# das_updated_v7.net
KiCad netlist of a schematic drawn in EAGLE
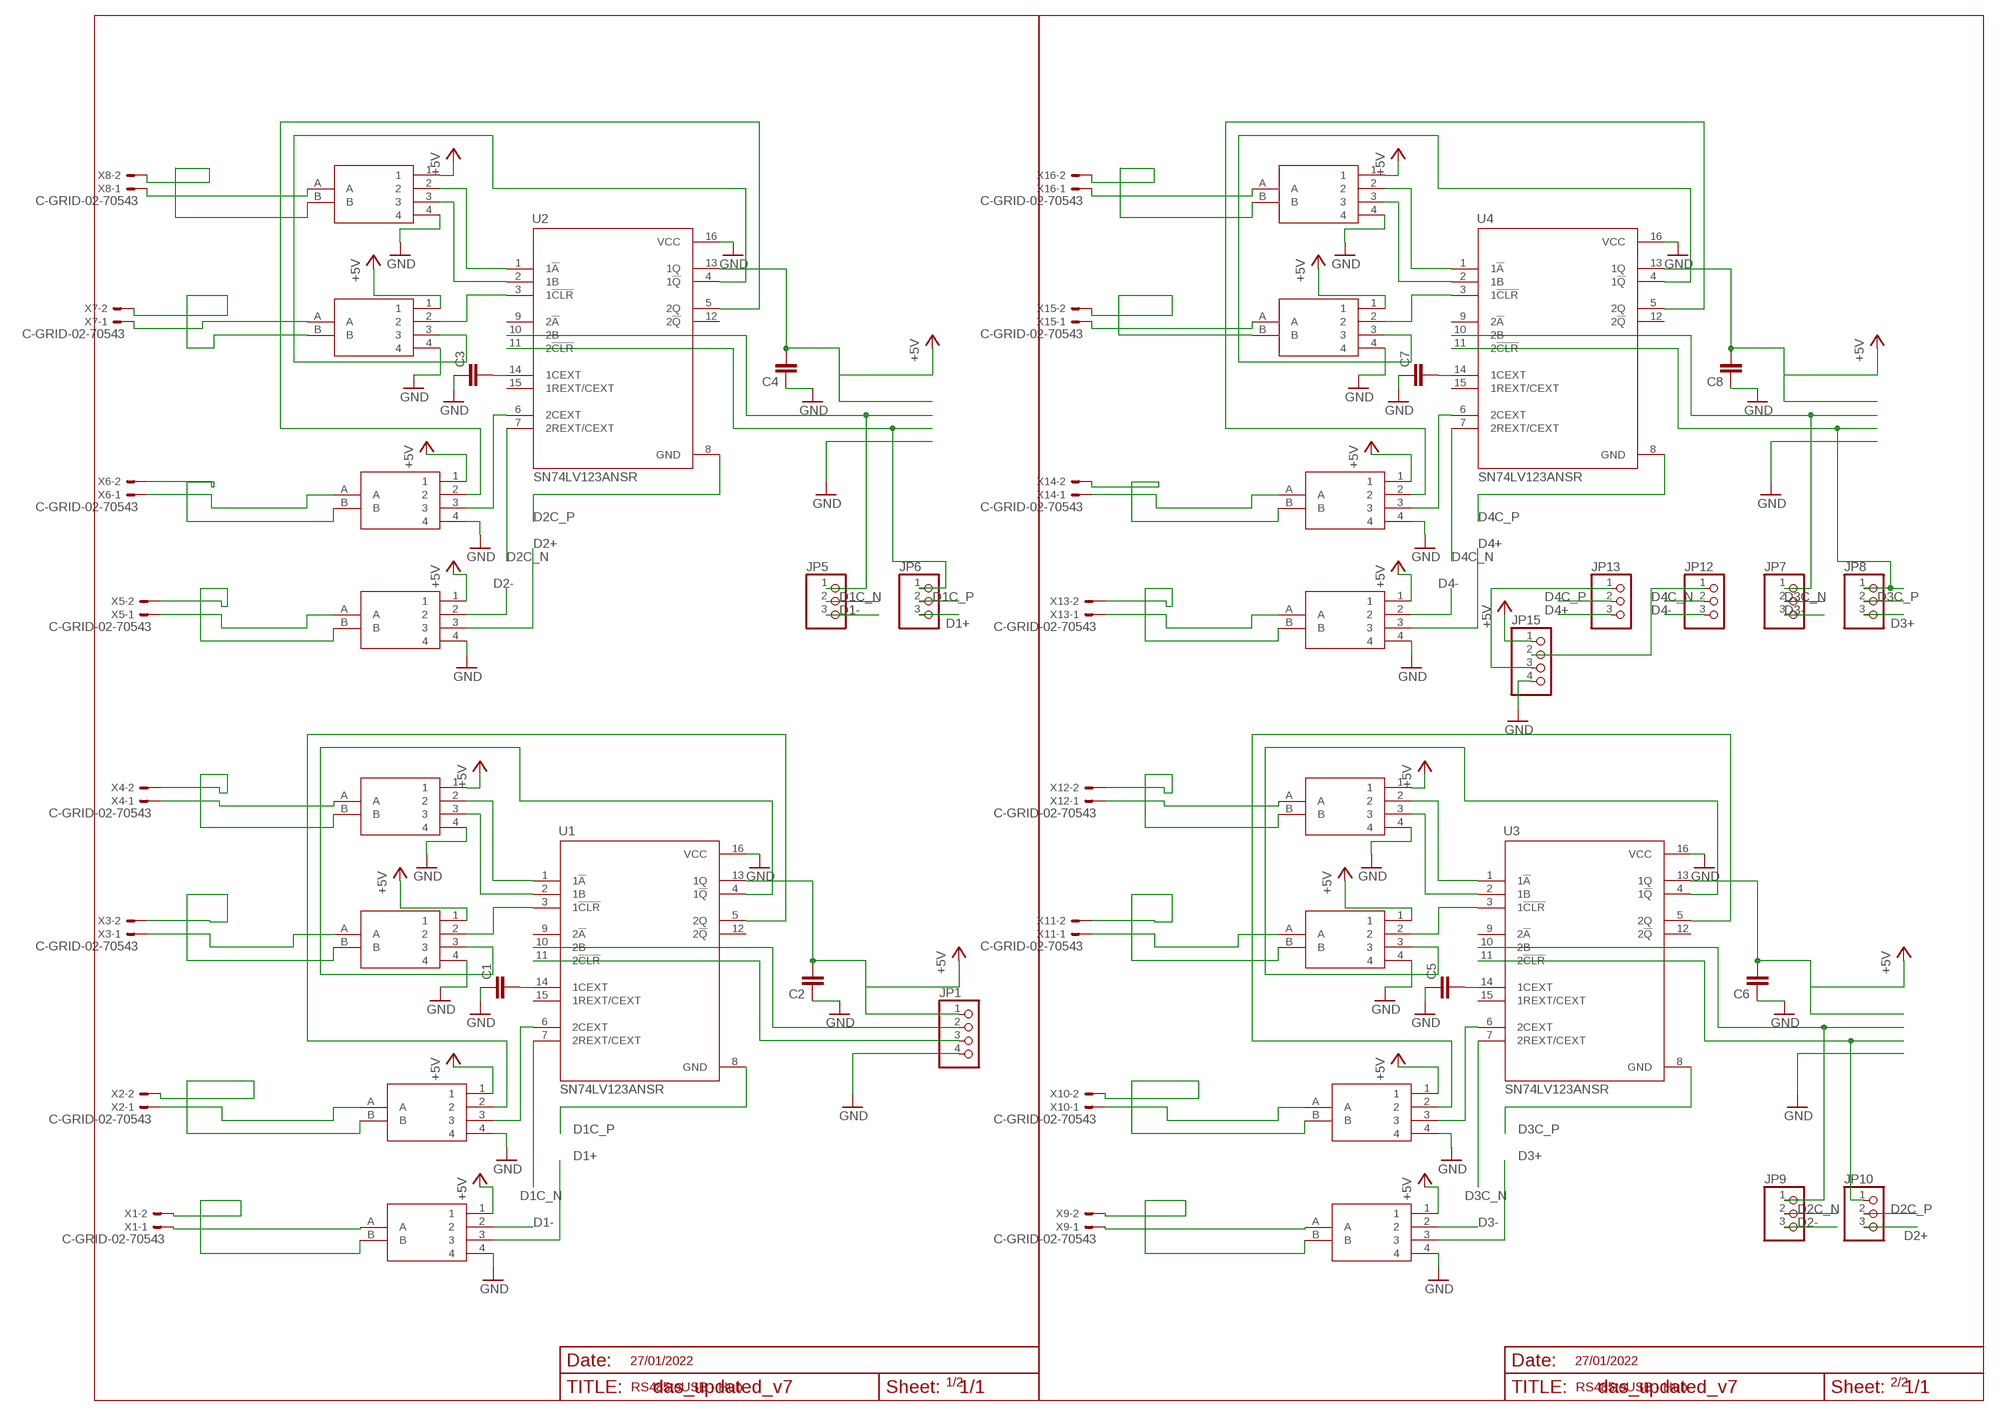
[diagram p0: schematic, sheet 1]

(export (version "E")
  (design (tool "Eeschema 10.0.6"))
  (components
    (comp (ref "C1")
      (value "C-EUC0603K")
      (footprint "eagle-import:C0603K")
      (libsource (lib "eagle-import") (part "C-EUC0603K"))
    )
    (comp (ref "C2")
      (value "C-EUC0603K")
      (footprint "eagle-import:C0603K")
      (libsource (lib "eagle-import") (part "C-EUC0603K"))
    )
    (comp (ref "C3")
      (value "C-EUC0603K")
      (footprint "eagle-import:C0603K")
      (libsource (lib "eagle-import") (part "C-EUC0603K"))
    )
    (comp (ref "C4")
      (value "C-EUC0603K")
      (footprint "eagle-import:C0603K")
      (libsource (lib "eagle-import") (part "C-EUC0603K"))
    )
    (comp (ref "C5")
      (value "C-EUC0603K")
      (footprint "eagle-import:C0603K")
      (libsource (lib "eagle-import") (part "C-EUC0603K"))
    )
    (comp (ref "C6")
      (value "C-EUC0603K")
      (footprint "eagle-import:C0603K")
      (libsource (lib "eagle-import") (part "C-EUC0603K"))
    )
    (comp (ref "C7")
      (value "C-EUC0603K")
      (footprint "eagle-import:C0603K")
      (libsource (lib "eagle-import") (part "C-EUC0603K"))
    )
    (comp (ref "C8")
      (value "C-EUC0603K")
      (footprint "eagle-import:C0603K")
      (libsource (lib "eagle-import") (part "C-EUC0603K"))
    )
    (comp (ref "JP1")
      (value "PINHD-1X4")
      (footprint "eagle-import:1X04")
      (libsource (lib "eagle-import") (part "PINHD-1X4"))
    )
    (comp (ref "JP5")
      (value "PINHD-1X3")
      (footprint "eagle-import:1X03")
      (libsource (lib "eagle-import") (part "PINHD-1X3"))
    )
    (comp (ref "JP6")
      (value "PINHD-1X3")
      (footprint "eagle-import:1X03")
      (libsource (lib "eagle-import") (part "PINHD-1X3"))
    )
    (comp (ref "JP7")
      (value "PINHD-1X3")
      (footprint "eagle-import:1X03")
      (libsource (lib "eagle-import") (part "PINHD-1X3"))
    )
    (comp (ref "JP8")
      (value "PINHD-1X3")
      (footprint "eagle-import:1X03")
      (libsource (lib "eagle-import") (part "PINHD-1X3"))
    )
    (comp (ref "JP9")
      (value "PINHD-1X3")
      (footprint "eagle-import:1X03")
      (libsource (lib "eagle-import") (part "PINHD-1X3"))
    )
    (comp (ref "JP10")
      (value "PINHD-1X3")
      (footprint "eagle-import:1X03")
      (libsource (lib "eagle-import") (part "PINHD-1X3"))
    )
    (comp (ref "JP12")
      (value "PINHD-1X3")
      (footprint "eagle-import:1X03")
      (libsource (lib "eagle-import") (part "PINHD-1X3"))
    )
    (comp (ref "JP13")
      (value "PINHD-1X3")
      (footprint "eagle-import:1X03")
      (libsource (lib "eagle-import") (part "PINHD-1X3"))
    )
    (comp (ref "JP15")
      (value "PINHD-1X4")
      (footprint "eagle-import:1X04")
      (libsource (lib "eagle-import") (part "PINHD-1X4"))
    )
    (comp (ref "U1")
      (value "SN74LV123ANSR")
      (footprint "eagle-import:SOIC127P780X200-16N")
      (fields (field (name "MF") "Texas Instruments"))
      (libsource (lib "eagle-import") (part "SN74LV123ANSR"))
    )
    (comp (ref "U2")
      (value "SN74LV123ANSR")
      (footprint "eagle-import:SOIC127P780X200-16N")
      (fields (field (name "MF") "Texas Instruments"))
      (libsource (lib "eagle-import") (part "SN74LV123ANSR"))
    )
    (comp (ref "U3")
      (value "SN74LV123ANSR")
      (footprint "eagle-import:SOIC127P780X200-16N")
      (fields (field (name "MF") "Texas Instruments"))
      (libsource (lib "eagle-import") (part "SN74LV123ANSR"))
    )
    (comp (ref "U4")
      (value "SN74LV123ANSR")
      (footprint "eagle-import:SOIC127P780X200-16N")
      (fields (field (name "MF") "Texas Instruments"))
      (libsource (lib "eagle-import") (part "SN74LV123ANSR"))
    )
    (comp (ref "USB2RS1")
      (value "USB2RS485")
      (footprint "eagle-import:USB2RS485")
      (libsource (lib "eagle-import") (part "USB2RS485"))
    )
    (comp (ref "USB2RS2")
      (value "USB2RS485")
      (footprint "eagle-import:USB2RS485")
      (libsource (lib "eagle-import") (part "USB2RS485"))
    )
    (comp (ref "USB2RS3")
      (value "USB2RS485")
      (footprint "eagle-import:USB2RS485")
      (libsource (lib "eagle-import") (part "USB2RS485"))
    )
    (comp (ref "USB2RS4")
      (value "USB2RS485")
      (footprint "eagle-import:USB2RS485")
      (libsource (lib "eagle-import") (part "USB2RS485"))
    )
    (comp (ref "USB2RS5")
      (value "USB2RS485")
      (footprint "eagle-import:USB2RS485")
      (libsource (lib "eagle-import") (part "USB2RS485"))
    )
    (comp (ref "USB2RS6")
      (value "USB2RS485")
      (footprint "eagle-import:USB2RS485")
      (libsource (lib "eagle-import") (part "USB2RS485"))
    )
    (comp (ref "USB2RS7")
      (value "USB2RS485")
      (footprint "eagle-import:USB2RS485")
      (libsource (lib "eagle-import") (part "USB2RS485"))
    )
    (comp (ref "USB2RS8")
      (value "USB2RS485")
      (footprint "eagle-import:USB2RS485")
      (libsource (lib "eagle-import") (part "USB2RS485"))
    )
    (comp (ref "USB2RS9")
      (value "USB2RS485")
      (footprint "eagle-import:USB2RS485")
      (libsource (lib "eagle-import") (part "USB2RS485"))
    )
    (comp (ref "USB2RS10")
      (value "USB2RS485")
      (footprint "eagle-import:USB2RS485")
      (libsource (lib "eagle-import") (part "USB2RS485"))
    )
    (comp (ref "USB2RS11")
      (value "USB2RS485")
      (footprint "eagle-import:USB2RS485")
      (libsource (lib "eagle-import") (part "USB2RS485"))
    )
    (comp (ref "USB2RS12")
      (value "USB2RS485")
      (footprint "eagle-import:USB2RS485")
      (libsource (lib "eagle-import") (part "USB2RS485"))
    )
    (comp (ref "USB2RS13")
      (value "USB2RS485")
      (footprint "eagle-import:USB2RS485")
      (libsource (lib "eagle-import") (part "USB2RS485"))
    )
    (comp (ref "USB2RS14")
      (value "USB2RS485")
      (footprint "eagle-import:USB2RS485")
      (libsource (lib "eagle-import") (part "USB2RS485"))
    )
    (comp (ref "USB2RS15")
      (value "USB2RS485")
      (footprint "eagle-import:USB2RS485")
      (libsource (lib "eagle-import") (part "USB2RS485"))
    )
    (comp (ref "USB2RS16")
      (value "USB2RS485")
      (footprint "eagle-import:USB2RS485")
      (libsource (lib "eagle-import") (part "USB2RS485"))
    )
    (comp (ref "X1")
      (value "C-GRID-02-70543")
      (footprint "eagle-import:70543-02")
      (fields (field (name "MF") "MOLEX"))
      (libsource (lib "eagle-import") (part "C-GRID-02-70543"))
    )
    (comp (ref "X2")
      (value "C-GRID-02-70543")
      (footprint "eagle-import:70543-02")
      (fields (field (name "MF") "MOLEX"))
      (libsource (lib "eagle-import") (part "C-GRID-02-70543"))
    )
    (comp (ref "X3")
      (value "C-GRID-02-70543")
      (footprint "eagle-import:70543-02")
      (fields (field (name "MF") "MOLEX"))
      (libsource (lib "eagle-import") (part "C-GRID-02-70543"))
    )
    (comp (ref "X4")
      (value "C-GRID-02-70543")
      (footprint "eagle-import:70543-02")
      (fields (field (name "MF") "MOLEX"))
      (libsource (lib "eagle-import") (part "C-GRID-02-70543"))
    )
    (comp (ref "X5")
      (value "C-GRID-02-70543")
      (footprint "eagle-import:70543-02")
      (fields (field (name "MF") "MOLEX"))
      (libsource (lib "eagle-import") (part "C-GRID-02-70543"))
    )
    (comp (ref "X6")
      (value "C-GRID-02-70543")
      (footprint "eagle-import:70543-02")
      (fields (field (name "MF") "MOLEX"))
      (libsource (lib "eagle-import") (part "C-GRID-02-70543"))
    )
    (comp (ref "X7")
      (value "C-GRID-02-70543")
      (footprint "eagle-import:70543-02")
      (fields (field (name "MF") "MOLEX"))
      (libsource (lib "eagle-import") (part "C-GRID-02-70543"))
    )
    (comp (ref "X8")
      (value "C-GRID-02-70543")
      (footprint "eagle-import:70543-02")
      (fields (field (name "MF") "MOLEX"))
      (libsource (lib "eagle-import") (part "C-GRID-02-70543"))
    )
    (comp (ref "X9")
      (value "C-GRID-02-70543")
      (footprint "eagle-import:70543-02")
      (fields (field (name "MF") "MOLEX"))
      (libsource (lib "eagle-import") (part "C-GRID-02-70543"))
    )
    (comp (ref "X10")
      (value "C-GRID-02-70543")
      (footprint "eagle-import:70543-02")
      (fields (field (name "MF") "MOLEX"))
      (libsource (lib "eagle-import") (part "C-GRID-02-70543"))
    )
    (comp (ref "X11")
      (value "C-GRID-02-70543")
      (footprint "eagle-import:70543-02")
      (fields (field (name "MF") "MOLEX"))
      (libsource (lib "eagle-import") (part "C-GRID-02-70543"))
    )
    (comp (ref "X12")
      (value "C-GRID-02-70543")
      (footprint "eagle-import:70543-02")
      (fields (field (name "MF") "MOLEX"))
      (libsource (lib "eagle-import") (part "C-GRID-02-70543"))
    )
    (comp (ref "X13")
      (value "C-GRID-02-70543")
      (footprint "eagle-import:70543-02")
      (fields (field (name "MF") "MOLEX"))
      (libsource (lib "eagle-import") (part "C-GRID-02-70543"))
    )
    (comp (ref "X14")
      (value "C-GRID-02-70543")
      (footprint "eagle-import:70543-02")
      (fields (field (name "MF") "MOLEX"))
      (libsource (lib "eagle-import") (part "C-GRID-02-70543"))
    )
    (comp (ref "X15")
      (value "C-GRID-02-70543")
      (footprint "eagle-import:70543-02")
      (fields (field (name "MF") "MOLEX"))
      (libsource (lib "eagle-import") (part "C-GRID-02-70543"))
    )
    (comp (ref "X16")
      (value "C-GRID-02-70543")
      (footprint "eagle-import:70543-02")
      (fields (field (name "MF") "MOLEX"))
      (libsource (lib "eagle-import") (part "C-GRID-02-70543"))
    )
  )
  (nets
    (net (code "1") (name "+5V") (class "Default")
      (node (ref "C2") (pin "2") (pinfunction "2_2") (pintype "passive"))
      (node (ref "C4") (pin "2") (pinfunction "2_2") (pintype "passive"))
      (node (ref "C6") (pin "2") (pinfunction "2_2") (pintype "passive"))
      (node (ref "C8") (pin "2") (pinfunction "2_2") (pintype "passive"))
      (node (ref "JP1") (pin "1") (pinfunction "1_1") (pintype "passive"))
      (node (ref "JP15") (pin "1") (pinfunction "1_1") (pintype "passive"))
      (node (ref "U1") (pin "13") (pinfunction "1Q_13") (pintype "output"))
      (node (ref "U2") (pin "13") (pinfunction "1Q_13") (pintype "output"))
      (node (ref "U3") (pin "13") (pinfunction "1Q_13") (pintype "output"))
      (node (ref "U4") (pin "13") (pinfunction "1Q_13") (pintype "output"))
      (node (ref "USB2RS1") (pin "1") (pinfunction "1_1") (pintype "bidirectional"))
      (node (ref "USB2RS10") (pin "1") (pinfunction "1_1") (pintype "bidirectional"))
      (node (ref "USB2RS11") (pin "1") (pinfunction "1_1") (pintype "bidirectional"))
      (node (ref "USB2RS12") (pin "1") (pinfunction "1_1") (pintype "bidirectional"))
      (node (ref "USB2RS13") (pin "1") (pinfunction "1_1") (pintype "bidirectional"))
      (node (ref "USB2RS14") (pin "1") (pinfunction "1_1") (pintype "bidirectional"))
      (node (ref "USB2RS15") (pin "1") (pinfunction "1_1") (pintype "bidirectional"))
      (node (ref "USB2RS16") (pin "1") (pinfunction "1_1") (pintype "bidirectional"))
      (node (ref "USB2RS2") (pin "1") (pinfunction "1_1") (pintype "bidirectional"))
      (node (ref "USB2RS3") (pin "1") (pinfunction "1_1") (pintype "bidirectional"))
      (node (ref "USB2RS4") (pin "1") (pinfunction "1_1") (pintype "bidirectional"))
      (node (ref "USB2RS5") (pin "1") (pinfunction "1_1") (pintype "bidirectional"))
      (node (ref "USB2RS6") (pin "1") (pinfunction "1_1") (pintype "bidirectional"))
      (node (ref "USB2RS7") (pin "1") (pinfunction "1_1") (pintype "bidirectional"))
      (node (ref "USB2RS8") (pin "1") (pinfunction "1_1") (pintype "bidirectional"))
      (node (ref "USB2RS9") (pin "1") (pinfunction "1_1") (pintype "bidirectional"))
    )
    (net (code "2") (name "/D1+") (class "Default")
      (node (ref "JP6") (pin "3") (pinfunction "3_3") (pintype "passive"))
      (node (ref "USB2RS4") (pin "3") (pinfunction "3_3") (pintype "bidirectional"))
    )
    (net (code "3") (name "/D1-") (class "Default")
      (node (ref "JP5") (pin "3") (pinfunction "3_3") (pintype "passive"))
      (node (ref "USB2RS4") (pin "2") (pinfunction "2_2") (pintype "bidirectional"))
    )
    (net (code "4") (name "/D1C_N") (class "Default")
      (node (ref "JP5") (pin "2") (pinfunction "2_2") (pintype "passive"))
      (node (ref "U1") (pin "7") (pinfunction "2REXT/CEXT_7") (pintype "bidirectional"))
    )
    (net (code "5") (name "/D1C_P") (class "Default")
      (node (ref "JP6") (pin "2") (pinfunction "2_2") (pintype "passive"))
      (node (ref "U1") (pin "8") (pinfunction "GND_8") (pintype "power_in"))
    )
    (net (code "6") (name "/D2+") (class "Default")
      (node (ref "JP10") (pin "3") (pinfunction "3_3") (pintype "passive"))
      (node (ref "USB2RS8") (pin "3") (pinfunction "3_3") (pintype "bidirectional"))
    )
    (net (code "7") (name "/D2-") (class "Default")
      (node (ref "JP9") (pin "3") (pinfunction "3_3") (pintype "passive"))
      (node (ref "USB2RS8") (pin "2") (pinfunction "2_2") (pintype "bidirectional"))
    )
    (net (code "8") (name "/D2C_N") (class "Default")
      (node (ref "JP9") (pin "2") (pinfunction "2_2") (pintype "passive"))
      (node (ref "U2") (pin "7") (pinfunction "2REXT/CEXT_7") (pintype "bidirectional"))
    )
    (net (code "9") (name "/D2C_P") (class "Default")
      (node (ref "JP10") (pin "2") (pinfunction "2_2") (pintype "passive"))
      (node (ref "U2") (pin "8") (pinfunction "GND_8") (pintype "power_in"))
    )
    (net (code "10") (name "/D3+") (class "Default")
      (node (ref "JP8") (pin "3") (pinfunction "3_3") (pintype "passive"))
      (node (ref "USB2RS12") (pin "3") (pinfunction "3_3") (pintype "bidirectional"))
    )
    (net (code "11") (name "/D3-") (class "Default")
      (node (ref "JP7") (pin "3") (pinfunction "3_3") (pintype "passive"))
      (node (ref "USB2RS12") (pin "2") (pinfunction "2_2") (pintype "bidirectional"))
    )
    (net (code "12") (name "/D3C_N") (class "Default")
      (node (ref "JP7") (pin "2") (pinfunction "2_2") (pintype "passive"))
      (node (ref "U3") (pin "7") (pinfunction "2REXT/CEXT_7") (pintype "bidirectional"))
    )
    (net (code "13") (name "/D3C_P") (class "Default")
      (node (ref "JP8") (pin "2") (pinfunction "2_2") (pintype "passive"))
      (node (ref "U3") (pin "8") (pinfunction "GND_8") (pintype "power_in"))
    )
    (net (code "14") (name "/D4+") (class "Default")
      (node (ref "JP13") (pin "3") (pinfunction "3_3") (pintype "passive"))
      (node (ref "USB2RS16") (pin "3") (pinfunction "3_3") (pintype "bidirectional"))
    )
    (net (code "15") (name "/D4-") (class "Default")
      (node (ref "JP12") (pin "3") (pinfunction "3_3") (pintype "passive"))
      (node (ref "USB2RS16") (pin "2") (pinfunction "2_2") (pintype "bidirectional"))
    )
    (net (code "16") (name "/D4C_N") (class "Default")
      (node (ref "JP12") (pin "2") (pinfunction "2_2") (pintype "passive"))
      (node (ref "U4") (pin "7") (pinfunction "2REXT/CEXT_7") (pintype "bidirectional"))
    )
    (net (code "17") (name "/D4C_P") (class "Default")
      (node (ref "JP13") (pin "2") (pinfunction "2_2") (pintype "passive"))
      (node (ref "U4") (pin "8") (pinfunction "GND_8") (pintype "power_in"))
    )
    (net (code "18") (name "GND") (class "Default")
      (node (ref "C1") (pin "1") (pinfunction "1_1") (pintype "passive"))
      (node (ref "C2") (pin "1") (pinfunction "1_1") (pintype "passive"))
      (node (ref "C3") (pin "1") (pinfunction "1_1") (pintype "passive"))
      (node (ref "C4") (pin "1") (pinfunction "1_1") (pintype "passive"))
      (node (ref "C5") (pin "1") (pinfunction "1_1") (pintype "passive"))
      (node (ref "C6") (pin "1") (pinfunction "1_1") (pintype "passive"))
      (node (ref "C7") (pin "1") (pinfunction "1_1") (pintype "passive"))
      (node (ref "C8") (pin "1") (pinfunction "1_1") (pintype "passive"))
      (node (ref "JP1") (pin "4") (pinfunction "4_4") (pintype "passive"))
      (node (ref "JP15") (pin "4") (pinfunction "4_4") (pintype "passive"))
      (node (ref "U1") (pin "16") (pinfunction "VCC_16") (pintype "power_in"))
      (node (ref "U2") (pin "16") (pinfunction "VCC_16") (pintype "power_in"))
      (node (ref "U3") (pin "16") (pinfunction "VCC_16") (pintype "power_in"))
      (node (ref "U4") (pin "16") (pinfunction "VCC_16") (pintype "power_in"))
      (node (ref "USB2RS1") (pin "4") (pinfunction "4_4") (pintype "bidirectional"))
      (node (ref "USB2RS10") (pin "4") (pinfunction "4_4") (pintype "bidirectional"))
      (node (ref "USB2RS11") (pin "4") (pinfunction "4_4") (pintype "bidirectional"))
      (node (ref "USB2RS12") (pin "4") (pinfunction "4_4") (pintype "bidirectional"))
      (node (ref "USB2RS13") (pin "4") (pinfunction "4_4") (pintype "bidirectional"))
      (node (ref "USB2RS14") (pin "4") (pinfunction "4_4") (pintype "bidirectional"))
      (node (ref "USB2RS15") (pin "4") (pinfunction "4_4") (pintype "bidirectional"))
      (node (ref "USB2RS16") (pin "4") (pinfunction "4_4") (pintype "bidirectional"))
      (node (ref "USB2RS2") (pin "4") (pinfunction "4_4") (pintype "bidirectional"))
      (node (ref "USB2RS3") (pin "4") (pinfunction "4_4") (pintype "bidirectional"))
      (node (ref "USB2RS4") (pin "4") (pinfunction "4_4") (pintype "bidirectional"))
      (node (ref "USB2RS5") (pin "4") (pinfunction "4_4") (pintype "bidirectional"))
      (node (ref "USB2RS6") (pin "4") (pinfunction "4_4") (pintype "bidirectional"))
      (node (ref "USB2RS7") (pin "4") (pinfunction "4_4") (pintype "bidirectional"))
      (node (ref "USB2RS8") (pin "4") (pinfunction "4_4") (pintype "bidirectional"))
      (node (ref "USB2RS9") (pin "4") (pinfunction "4_4") (pintype "bidirectional"))
    )
    (net (code "19") (name "Net-(JP12-Pad1)") (class "Default")
      (node (ref "JP12") (pin "1") (pinfunction "1_1") (pintype "passive"))
      (node (ref "JP15") (pin "2") (pinfunction "2_2") (pintype "passive"))
    )
    (net (code "20") (name "Net-(JP13-Pad1)") (class "Default")
      (node (ref "JP13") (pin "1") (pinfunction "1_1") (pintype "passive"))
      (node (ref "JP15") (pin "3") (pinfunction "3_3") (pintype "passive"))
    )
    (net (code "21") (name "Net-(U1-1B)") (class "Default")
      (node (ref "U1") (pin "2") (pinfunction "1B_2") (pintype "input"))
      (node (ref "USB2RS1") (pin "3") (pinfunction "3_3") (pintype "bidirectional"))
    )
    (net (code "22") (name "Net-(U1-1CEXT)") (class "Default")
      (node (ref "C1") (pin "2") (pinfunction "2_2") (pintype "passive"))
      (node (ref "U1") (pin "14") (pinfunction "1CEXT_14") (pintype "bidirectional"))
    )
    (net (code "23") (name "Net-(U1-1~{A})") (class "Default")
      (node (ref "U1") (pin "1") (pinfunction "1~{A}_1") (pintype "input"))
      (node (ref "USB2RS1") (pin "2") (pinfunction "2_2") (pintype "bidirectional"))
    )
    (net (code "24") (name "Net-(U1-1~{CLR})") (class "Default")
      (node (ref "U1") (pin "3") (pinfunction "1~{CLR}_3") (pintype "input"))
      (node (ref "USB2RS2") (pin "2") (pinfunction "2_2") (pintype "bidirectional"))
    )
    (net (code "25") (name "Net-(U1-1~{Q})") (class "Default")
      (node (ref "U1") (pin "4") (pinfunction "1~{Q}_4") (pintype "output"))
      (node (ref "USB2RS2") (pin "3") (pinfunction "3_3") (pintype "bidirectional"))
    )
    (net (code "26") (name "Net-(U1-2B)") (class "Default")
      (node (ref "JP1") (pin "2") (pinfunction "2_2") (pintype "passive"))
      (node (ref "U1") (pin "10") (pinfunction "2B_10") (pintype "input"))
    )
    (net (code "27") (name "Net-(U1-2CEXT)") (class "Default")
      (node (ref "U1") (pin "6") (pinfunction "2CEXT_6") (pintype "bidirectional"))
      (node (ref "USB2RS3") (pin "3") (pinfunction "3_3") (pintype "bidirectional"))
    )
    (net (code "28") (name "Net-(U1-2Q)") (class "Default")
      (node (ref "U1") (pin "5") (pinfunction "2Q_5") (pintype "output"))
      (node (ref "USB2RS3") (pin "2") (pinfunction "2_2") (pintype "bidirectional"))
    )
    (net (code "29") (name "Net-(U1-2~{CLR})") (class "Default")
      (node (ref "JP1") (pin "3") (pinfunction "3_3") (pintype "passive"))
      (node (ref "U1") (pin "11") (pinfunction "2~{CLR}_11") (pintype "input"))
    )
    (net (code "30") (name "Net-(U2-1B)") (class "Default")
      (node (ref "U2") (pin "2") (pinfunction "1B_2") (pintype "input"))
      (node (ref "USB2RS5") (pin "3") (pinfunction "3_3") (pintype "bidirectional"))
    )
    (net (code "31") (name "Net-(U2-1CEXT)") (class "Default")
      (node (ref "C3") (pin "2") (pinfunction "2_2") (pintype "passive"))
      (node (ref "U2") (pin "14") (pinfunction "1CEXT_14") (pintype "bidirectional"))
    )
    (net (code "32") (name "Net-(U2-1~{A})") (class "Default")
      (node (ref "U2") (pin "1") (pinfunction "1~{A}_1") (pintype "input"))
      (node (ref "USB2RS5") (pin "2") (pinfunction "2_2") (pintype "bidirectional"))
    )
    (net (code "33") (name "Net-(U2-1~{CLR})") (class "Default")
      (node (ref "U2") (pin "3") (pinfunction "1~{CLR}_3") (pintype "input"))
      (node (ref "USB2RS6") (pin "2") (pinfunction "2_2") (pintype "bidirectional"))
    )
    (net (code "34") (name "Net-(U2-1~{Q})") (class "Default")
      (node (ref "U2") (pin "4") (pinfunction "1~{Q}_4") (pintype "output"))
      (node (ref "USB2RS6") (pin "3") (pinfunction "3_3") (pintype "bidirectional"))
    )
    (net (code "35") (name "Net-(U2-2B)") (class "Default")
      (node (ref "JP5") (pin "1") (pinfunction "1_1") (pintype "passive"))
      (node (ref "U2") (pin "10") (pinfunction "2B_10") (pintype "input"))
    )
    (net (code "36") (name "Net-(U2-2CEXT)") (class "Default")
      (node (ref "U2") (pin "6") (pinfunction "2CEXT_6") (pintype "bidirectional"))
      (node (ref "USB2RS7") (pin "3") (pinfunction "3_3") (pintype "bidirectional"))
    )
    (net (code "37") (name "Net-(U2-2Q)") (class "Default")
      (node (ref "U2") (pin "5") (pinfunction "2Q_5") (pintype "output"))
      (node (ref "USB2RS7") (pin "2") (pinfunction "2_2") (pintype "bidirectional"))
    )
    (net (code "38") (name "Net-(U2-2~{CLR})") (class "Default")
      (node (ref "JP6") (pin "1") (pinfunction "1_1") (pintype "passive"))
      (node (ref "U2") (pin "11") (pinfunction "2~{CLR}_11") (pintype "input"))
    )
    (net (code "39") (name "Net-(U3-1B)") (class "Default")
      (node (ref "U3") (pin "2") (pinfunction "1B_2") (pintype "input"))
      (node (ref "USB2RS9") (pin "3") (pinfunction "3_3") (pintype "bidirectional"))
    )
    (net (code "40") (name "Net-(U3-1CEXT)") (class "Default")
      (node (ref "C5") (pin "2") (pinfunction "2_2") (pintype "passive"))
      (node (ref "U3") (pin "14") (pinfunction "1CEXT_14") (pintype "bidirectional"))
    )
    (net (code "41") (name "Net-(U3-1~{A})") (class "Default")
      (node (ref "U3") (pin "1") (pinfunction "1~{A}_1") (pintype "input"))
      (node (ref "USB2RS9") (pin "2") (pinfunction "2_2") (pintype "bidirectional"))
    )
    (net (code "42") (name "Net-(U3-1~{CLR})") (class "Default")
      (node (ref "U3") (pin "3") (pinfunction "1~{CLR}_3") (pintype "input"))
      (node (ref "USB2RS10") (pin "2") (pinfunction "2_2") (pintype "bidirectional"))
    )
    (net (code "43") (name "Net-(U3-1~{Q})") (class "Default")
      (node (ref "U3") (pin "4") (pinfunction "1~{Q}_4") (pintype "output"))
      (node (ref "USB2RS10") (pin "3") (pinfunction "3_3") (pintype "bidirectional"))
    )
    (net (code "44") (name "Net-(U3-2B)") (class "Default")
      (node (ref "JP9") (pin "1") (pinfunction "1_1") (pintype "passive"))
      (node (ref "U3") (pin "10") (pinfunction "2B_10") (pintype "input"))
    )
    (net (code "45") (name "Net-(U3-2CEXT)") (class "Default")
      (node (ref "U3") (pin "6") (pinfunction "2CEXT_6") (pintype "bidirectional"))
      (node (ref "USB2RS11") (pin "3") (pinfunction "3_3") (pintype "bidirectional"))
    )
    (net (code "46") (name "Net-(U3-2Q)") (class "Default")
      (node (ref "U3") (pin "5") (pinfunction "2Q_5") (pintype "output"))
      (node (ref "USB2RS11") (pin "2") (pinfunction "2_2") (pintype "bidirectional"))
    )
    (net (code "47") (name "Net-(U3-2~{CLR})") (class "Default")
      (node (ref "JP10") (pin "1") (pinfunction "1_1") (pintype "passive"))
      (node (ref "U3") (pin "11") (pinfunction "2~{CLR}_11") (pintype "input"))
    )
    (net (code "48") (name "Net-(U4-1B)") (class "Default")
      (node (ref "U4") (pin "2") (pinfunction "1B_2") (pintype "input"))
      (node (ref "USB2RS13") (pin "3") (pinfunction "3_3") (pintype "bidirectional"))
    )
    (net (code "49") (name "Net-(U4-1CEXT)") (class "Default")
      (node (ref "C7") (pin "2") (pinfunction "2_2") (pintype "passive"))
      (node (ref "U4") (pin "14") (pinfunction "1CEXT_14") (pintype "bidirectional"))
    )
    (net (code "50") (name "Net-(U4-1~{A})") (class "Default")
      (node (ref "U4") (pin "1") (pinfunction "1~{A}_1") (pintype "input"))
      (node (ref "USB2RS13") (pin "2") (pinfunction "2_2") (pintype "bidirectional"))
    )
    (net (code "51") (name "Net-(U4-1~{CLR})") (class "Default")
      (node (ref "U4") (pin "3") (pinfunction "1~{CLR}_3") (pintype "input"))
      (node (ref "USB2RS14") (pin "2") (pinfunction "2_2") (pintype "bidirectional"))
    )
    (net (code "52") (name "Net-(U4-1~{Q})") (class "Default")
      (node (ref "U4") (pin "4") (pinfunction "1~{Q}_4") (pintype "output"))
      (node (ref "USB2RS14") (pin "3") (pinfunction "3_3") (pintype "bidirectional"))
    )
    (net (code "53") (name "Net-(U4-2B)") (class "Default")
      (node (ref "JP7") (pin "1") (pinfunction "1_1") (pintype "passive"))
      (node (ref "U4") (pin "10") (pinfunction "2B_10") (pintype "input"))
    )
    (net (code "54") (name "Net-(U4-2CEXT)") (class "Default")
      (node (ref "U4") (pin "6") (pinfunction "2CEXT_6") (pintype "bidirectional"))
      (node (ref "USB2RS15") (pin "3") (pinfunction "3_3") (pintype "bidirectional"))
    )
    (net (code "55") (name "Net-(U4-2Q)") (class "Default")
      (node (ref "U4") (pin "5") (pinfunction "2Q_5") (pintype "output"))
      (node (ref "USB2RS15") (pin "2") (pinfunction "2_2") (pintype "bidirectional"))
    )
    (net (code "56") (name "Net-(U4-2~{CLR})") (class "Default")
      (node (ref "JP8") (pin "1") (pinfunction "1_1") (pintype "passive"))
      (node (ref "U4") (pin "11") (pinfunction "2~{CLR}_11") (pintype "input"))
    )
    (net (code "57") (name "Net-(X1A-S)") (class "Default")
      (node (ref "USB2RS4") (pin "A") (pinfunction "A_A") (pintype "bidirectional"))
      (node (ref "X1") (pin "1") (pinfunction "S_1") (pintype "passive"))
    )
    (net (code "58") (name "Net-(X1B-S)") (class "Default")
      (node (ref "USB2RS4") (pin "B") (pinfunction "B_B") (pintype "bidirectional"))
      (node (ref "X1") (pin "2") (pinfunction "S_2") (pintype "passive"))
    )
    (net (code "59") (name "Net-(X2A-S)") (class "Default")
      (node (ref "USB2RS3") (pin "A") (pinfunction "A_A") (pintype "bidirectional"))
      (node (ref "X2") (pin "1") (pinfunction "S_1") (pintype "passive"))
    )
    (net (code "60") (name "Net-(X2B-S)") (class "Default")
      (node (ref "USB2RS3") (pin "B") (pinfunction "B_B") (pintype "bidirectional"))
      (node (ref "X2") (pin "2") (pinfunction "S_2") (pintype "passive"))
    )
    (net (code "61") (name "Net-(X3A-S)") (class "Default")
      (node (ref "USB2RS2") (pin "A") (pinfunction "A_A") (pintype "bidirectional"))
      (node (ref "X3") (pin "1") (pinfunction "S_1") (pintype "passive"))
    )
    (net (code "62") (name "Net-(X3B-S)") (class "Default")
      (node (ref "USB2RS2") (pin "B") (pinfunction "B_B") (pintype "bidirectional"))
      (node (ref "X3") (pin "2") (pinfunction "S_2") (pintype "passive"))
    )
    (net (code "63") (name "Net-(X4A-S)") (class "Default")
      (node (ref "USB2RS1") (pin "A") (pinfunction "A_A") (pintype "bidirectional"))
      (node (ref "X4") (pin "1") (pinfunction "S_1") (pintype "passive"))
    )
    (net (code "64") (name "Net-(X4B-S)") (class "Default")
      (node (ref "USB2RS1") (pin "B") (pinfunction "B_B") (pintype "bidirectional"))
      (node (ref "X4") (pin "2") (pinfunction "S_2") (pintype "passive"))
    )
    (net (code "65") (name "Net-(X5A-S)") (class "Default")
      (node (ref "USB2RS8") (pin "A") (pinfunction "A_A") (pintype "bidirectional"))
      (node (ref "X5") (pin "1") (pinfunction "S_1") (pintype "passive"))
    )
    (net (code "66") (name "Net-(X5B-S)") (class "Default")
      (node (ref "USB2RS8") (pin "B") (pinfunction "B_B") (pintype "bidirectional"))
      (node (ref "X5") (pin "2") (pinfunction "S_2") (pintype "passive"))
    )
    (net (code "67") (name "Net-(X6A-S)") (class "Default")
      (node (ref "USB2RS7") (pin "A") (pinfunction "A_A") (pintype "bidirectional"))
      (node (ref "X6") (pin "1") (pinfunction "S_1") (pintype "passive"))
    )
    (net (code "68") (name "Net-(X6B-S)") (class "Default")
      (node (ref "USB2RS7") (pin "B") (pinfunction "B_B") (pintype "bidirectional"))
      (node (ref "X6") (pin "2") (pinfunction "S_2") (pintype "passive"))
    )
    (net (code "69") (name "Net-(X7A-S)") (class "Default")
      (node (ref "USB2RS6") (pin "A") (pinfunction "A_A") (pintype "bidirectional"))
      (node (ref "X7") (pin "1") (pinfunction "S_1") (pintype "passive"))
    )
    (net (code "70") (name "Net-(X7B-S)") (class "Default")
      (node (ref "USB2RS6") (pin "B") (pinfunction "B_B") (pintype "bidirectional"))
      (node (ref "X7") (pin "2") (pinfunction "S_2") (pintype "passive"))
    )
    (net (code "71") (name "Net-(X8A-S)") (class "Default")
      (node (ref "USB2RS5") (pin "A") (pinfunction "A_A") (pintype "bidirectional"))
      (node (ref "X8") (pin "1") (pinfunction "S_1") (pintype "passive"))
    )
    (net (code "72") (name "Net-(X8B-S)") (class "Default")
      (node (ref "USB2RS5") (pin "B") (pinfunction "B_B") (pintype "bidirectional"))
      (node (ref "X8") (pin "2") (pinfunction "S_2") (pintype "passive"))
    )
    (net (code "73") (name "Net-(X9A-S)") (class "Default")
      (node (ref "USB2RS12") (pin "A") (pinfunction "A_A") (pintype "bidirectional"))
      (node (ref "X9") (pin "1") (pinfunction "S_1") (pintype "passive"))
    )
    (net (code "74") (name "Net-(X9B-S)") (class "Default")
      (node (ref "USB2RS12") (pin "B") (pinfunction "B_B") (pintype "bidirectional"))
      (node (ref "X9") (pin "2") (pinfunction "S_2") (pintype "passive"))
    )
    (net (code "75") (name "Net-(X10A-S)") (class "Default")
      (node (ref "USB2RS11") (pin "A") (pinfunction "A_A") (pintype "bidirectional"))
      (node (ref "X10") (pin "1") (pinfunction "S_1") (pintype "passive"))
    )
    (net (code "76") (name "Net-(X10B-S)") (class "Default")
      (node (ref "USB2RS11") (pin "B") (pinfunction "B_B") (pintype "bidirectional"))
      (node (ref "X10") (pin "2") (pinfunction "S_2") (pintype "passive"))
    )
    (net (code "77") (name "Net-(X11A-S)") (class "Default")
      (node (ref "USB2RS10") (pin "A") (pinfunction "A_A") (pintype "bidirectional"))
      (node (ref "X11") (pin "1") (pinfunction "S_1") (pintype "passive"))
    )
    (net (code "78") (name "Net-(X11B-S)") (class "Default")
      (node (ref "USB2RS10") (pin "B") (pinfunction "B_B") (pintype "bidirectional"))
      (node (ref "X11") (pin "2") (pinfunction "S_2") (pintype "passive"))
    )
    (net (code "79") (name "Net-(X12A-S)") (class "Default")
      (node (ref "USB2RS9") (pin "A") (pinfunction "A_A") (pintype "bidirectional"))
      (node (ref "X12") (pin "1") (pinfunction "S_1") (pintype "passive"))
    )
    (net (code "80") (name "Net-(X12B-S)") (class "Default")
      (node (ref "USB2RS9") (pin "B") (pinfunction "B_B") (pintype "bidirectional"))
      (node (ref "X12") (pin "2") (pinfunction "S_2") (pintype "passive"))
    )
    (net (code "81") (name "Net-(X13A-S)") (class "Default")
      (node (ref "USB2RS16") (pin "A") (pinfunction "A_A") (pintype "bidirectional"))
      (node (ref "X13") (pin "1") (pinfunction "S_1") (pintype "passive"))
    )
    (net (code "82") (name "Net-(X13B-S)") (class "Default")
      (node (ref "USB2RS16") (pin "B") (pinfunction "B_B") (pintype "bidirectional"))
      (node (ref "X13") (pin "2") (pinfunction "S_2") (pintype "passive"))
    )
    (net (code "83") (name "Net-(X14A-S)") (class "Default")
      (node (ref "USB2RS15") (pin "A") (pinfunction "A_A") (pintype "bidirectional"))
      (node (ref "X14") (pin "1") (pinfunction "S_1") (pintype "passive"))
    )
    (net (code "84") (name "Net-(X14B-S)") (class "Default")
      (node (ref "USB2RS15") (pin "B") (pinfunction "B_B") (pintype "bidirectional"))
      (node (ref "X14") (pin "2") (pinfunction "S_2") (pintype "passive"))
    )
    (net (code "85") (name "Net-(X15A-S)") (class "Default")
      (node (ref "USB2RS14") (pin "A") (pinfunction "A_A") (pintype "bidirectional"))
      (node (ref "X15") (pin "1") (pinfunction "S_1") (pintype "passive"))
    )
    (net (code "86") (name "Net-(X15B-S)") (class "Default")
      (node (ref "USB2RS14") (pin "B") (pinfunction "B_B") (pintype "bidirectional"))
      (node (ref "X15") (pin "2") (pinfunction "S_2") (pintype "passive"))
    )
    (net (code "87") (name "Net-(X16A-S)") (class "Default")
      (node (ref "USB2RS13") (pin "A") (pinfunction "A_A") (pintype "bidirectional"))
      (node (ref "X16") (pin "1") (pinfunction "S_1") (pintype "passive"))
    )
    (net (code "88") (name "Net-(X16B-S)") (class "Default")
      (node (ref "USB2RS13") (pin "B") (pinfunction "B_B") (pintype "bidirectional"))
      (node (ref "X16") (pin "2") (pinfunction "S_2") (pintype "passive"))
    )
    (net (code "89") (name "unconnected-(U1-1REXT{slash}CEXT-Pad15)") (class "Default")
      (node (ref "U1") (pin "15") (pinfunction "1REXT/CEXT_15") (pintype "bidirectional"))
    )
    (net (code "90") (name "unconnected-(U1-2~{A}-Pad9)") (class "Default")
      (node (ref "U1") (pin "9") (pinfunction "2~{A}_9") (pintype "input"))
    )
    (net (code "91") (name "unconnected-(U1-2~{Q}-Pad12)") (class "Default")
      (node (ref "U1") (pin "12") (pinfunction "2~{Q}_12") (pintype "output"))
    )
    (net (code "92") (name "unconnected-(U2-1REXT{slash}CEXT-Pad15)") (class "Default")
      (node (ref "U2") (pin "15") (pinfunction "1REXT/CEXT_15") (pintype "bidirectional"))
    )
    (net (code "93") (name "unconnected-(U2-2~{A}-Pad9)") (class "Default")
      (node (ref "U2") (pin "9") (pinfunction "2~{A}_9") (pintype "input"))
    )
    (net (code "94") (name "unconnected-(U2-2~{Q}-Pad12)") (class "Default")
      (node (ref "U2") (pin "12") (pinfunction "2~{Q}_12") (pintype "output"))
    )
    (net (code "95") (name "unconnected-(U3-1REXT{slash}CEXT-Pad15)") (class "Default")
      (node (ref "U3") (pin "15") (pinfunction "1REXT/CEXT_15") (pintype "bidirectional"))
    )
    (net (code "96") (name "unconnected-(U3-2~{A}-Pad9)") (class "Default")
      (node (ref "U3") (pin "9") (pinfunction "2~{A}_9") (pintype "input"))
    )
    (net (code "97") (name "unconnected-(U3-2~{Q}-Pad12)") (class "Default")
      (node (ref "U3") (pin "12") (pinfunction "2~{Q}_12") (pintype "output"))
    )
    (net (code "98") (name "unconnected-(U4-1REXT{slash}CEXT-Pad15)") (class "Default")
      (node (ref "U4") (pin "15") (pinfunction "1REXT/CEXT_15") (pintype "bidirectional"))
    )
    (net (code "99") (name "unconnected-(U4-2~{A}-Pad9)") (class "Default")
      (node (ref "U4") (pin "9") (pinfunction "2~{A}_9") (pintype "input"))
    )
    (net (code "100") (name "unconnected-(U4-2~{Q}-Pad12)") (class "Default")
      (node (ref "U4") (pin "12") (pinfunction "2~{Q}_12") (pintype "output"))
    )
  )
)
